# Transceiver.net
KiCad netlist of a schematic drawn in Altium Designer
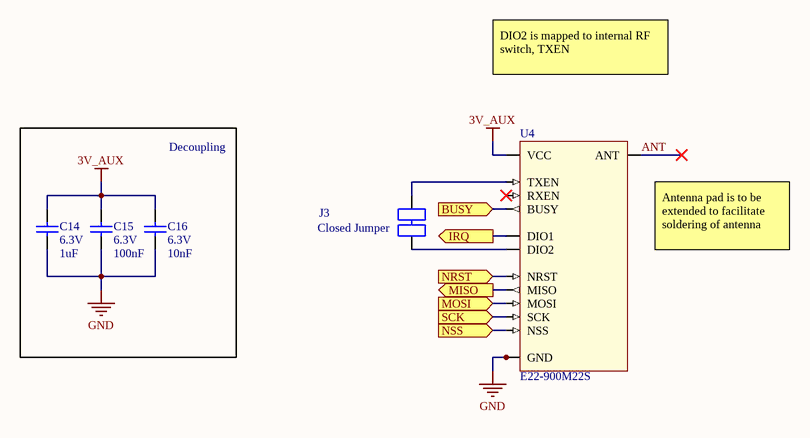
[diagram p0: Transceiver.SchDoc]

(export (version "E")
  (design (tool "Eeschema 10.0.6"))
  (components
    (comp (ref "C14")
      (value "1uF")
      (footprint "0603 (1608M)")
      (description "Capacitor")
      (fields (field (name "VOLTAGE") "6.3V") (field (name "Comment") "Cap"))
      (libsource (lib "components") (part "Cap"))
    )
    (comp (ref "C15")
      (value "100nF")
      (footprint "0603 (1608M)")
      (description "Capacitor")
      (fields (field (name "VOLTAGE") "6.3V") (field (name "Comment") "Cap"))
      (libsource (lib "components") (part "Cap"))
    )
    (comp (ref "C16")
      (value "10nF")
      (footprint "0603 (1608M)")
      (description "Capacitor")
      (fields (field (name "VOLTAGE") "6.3V") (field (name "Comment") "Cap"))
      (libsource (lib "components") (part "Cap"))
    )
    (comp (ref "J3")
      (value "Closed Jumper")
      (footprint "Jumper (Close)")
      (libsource (lib "components") (part "Jumper (Closed)"))
    )
    (comp (ref "U4")
      (value "E22-900M22S")
      (footprint "E22-900M22S")
      (description "SX1262-based Wireless Module")
      (libsource (lib "components") (part "E22-900M22S"))
    )
  )
  (nets
    (net (code "1") (name "/ANT") (class "Default")
      (node (ref "U4") (pin "21") (pinfunction "ANT_21") (pintype "passive+no_connect"))
    )
    (net (code "2") (name "/BUSY") (class "Default")
      (node (ref "U4") (pin "14") (pinfunction "BUSY_14") (pintype "output"))
    )
    (net (code "3") (name "/IRQ") (class "Default")
      (node (ref "U4") (pin "13") (pinfunction "DIO1_13") (pintype "bidirectional"))
    )
    (net (code "4") (name "/MISO") (class "Default")
      (node (ref "U4") (pin "16") (pinfunction "MISO_16") (pintype "output"))
    )
    (net (code "5") (name "/MOSI") (class "Default")
      (node (ref "U4") (pin "17") (pinfunction "MOSI_17") (pintype "input"))
    )
    (net (code "6") (name "/NRST") (class "Default")
      (node (ref "U4") (pin "15") (pinfunction "NRST_15") (pintype "input"))
    )
    (net (code "7") (name "/NSS") (class "Default")
      (node (ref "U4") (pin "19") (pinfunction "NSS_19") (pintype "input"))
    )
    (net (code "8") (name "/SCK") (class "Default")
      (node (ref "U4") (pin "18") (pinfunction "SCK_18") (pintype "input"))
    )
    (net (code "9") (name "3V_AUX") (class "Default")
      (node (ref "C14") (pin "2") (pinfunction "2_2") (pintype "passive"))
      (node (ref "C15") (pin "2") (pinfunction "2_2") (pintype "passive"))
      (node (ref "C16") (pin "2") (pinfunction "2_2") (pintype "passive"))
      (node (ref "U4") (pin "9") (pinfunction "VCC_9") (pintype "power_in"))
    )
    (net (code "10") (name "GND") (class "Default")
      (node (ref "C14") (pin "1") (pinfunction "1_1") (pintype "passive"))
      (node (ref "C15") (pin "1") (pinfunction "1_1") (pintype "passive"))
      (node (ref "C16") (pin "1") (pinfunction "1_1") (pintype "passive"))
      (node (ref "U4") (pin "1") (pinfunction "GND_1") (pintype "power_in"))
      (node (ref "U4") (pin "10") (pinfunction "GND_10") (pintype "power_in"))
      (node (ref "U4") (pin "11") (pinfunction "GND_11") (pintype "power_in"))
      (node (ref "U4") (pin "12") (pinfunction "GND_12") (pintype "power_in"))
      (node (ref "U4") (pin "2") (pinfunction "GND_2") (pintype "power_in"))
      (node (ref "U4") (pin "20") (pinfunction "GND_20") (pintype "power_in"))
      (node (ref "U4") (pin "22") (pinfunction "GND_22") (pintype "power_in"))
      (node (ref "U4") (pin "3") (pinfunction "GND_3") (pintype "power_in"))
      (node (ref "U4") (pin "4") (pinfunction "GND_4") (pintype "power_in"))
      (node (ref "U4") (pin "5") (pinfunction "GND_5") (pintype "power_in"))
    )
    (net (code "11") (name "Net-(U4-DIO2)") (class "Default")
      (node (ref "J3") (pin "1") (pinfunction "1_1") (pintype "passive"))
      (node (ref "U4") (pin "8") (pinfunction "DIO2_8") (pintype "bidirectional"))
    )
    (net (code "12") (name "Net-(U4-TXEN)") (class "Default")
      (node (ref "J3") (pin "2") (pinfunction "2_2") (pintype "passive"))
      (node (ref "U4") (pin "7") (pinfunction "TXEN_7") (pintype "input"))
    )
    (net (code "13") (name "unconnected-(U4-RXEN-Pad6)") (class "Default")
      (node (ref "U4") (pin "6") (pinfunction "RXEN_6") (pintype "input+no_connect"))
    )
  )
)
